# MicrofluidicsController.net
KiCad netlist of a schematic drawn in EAGLE
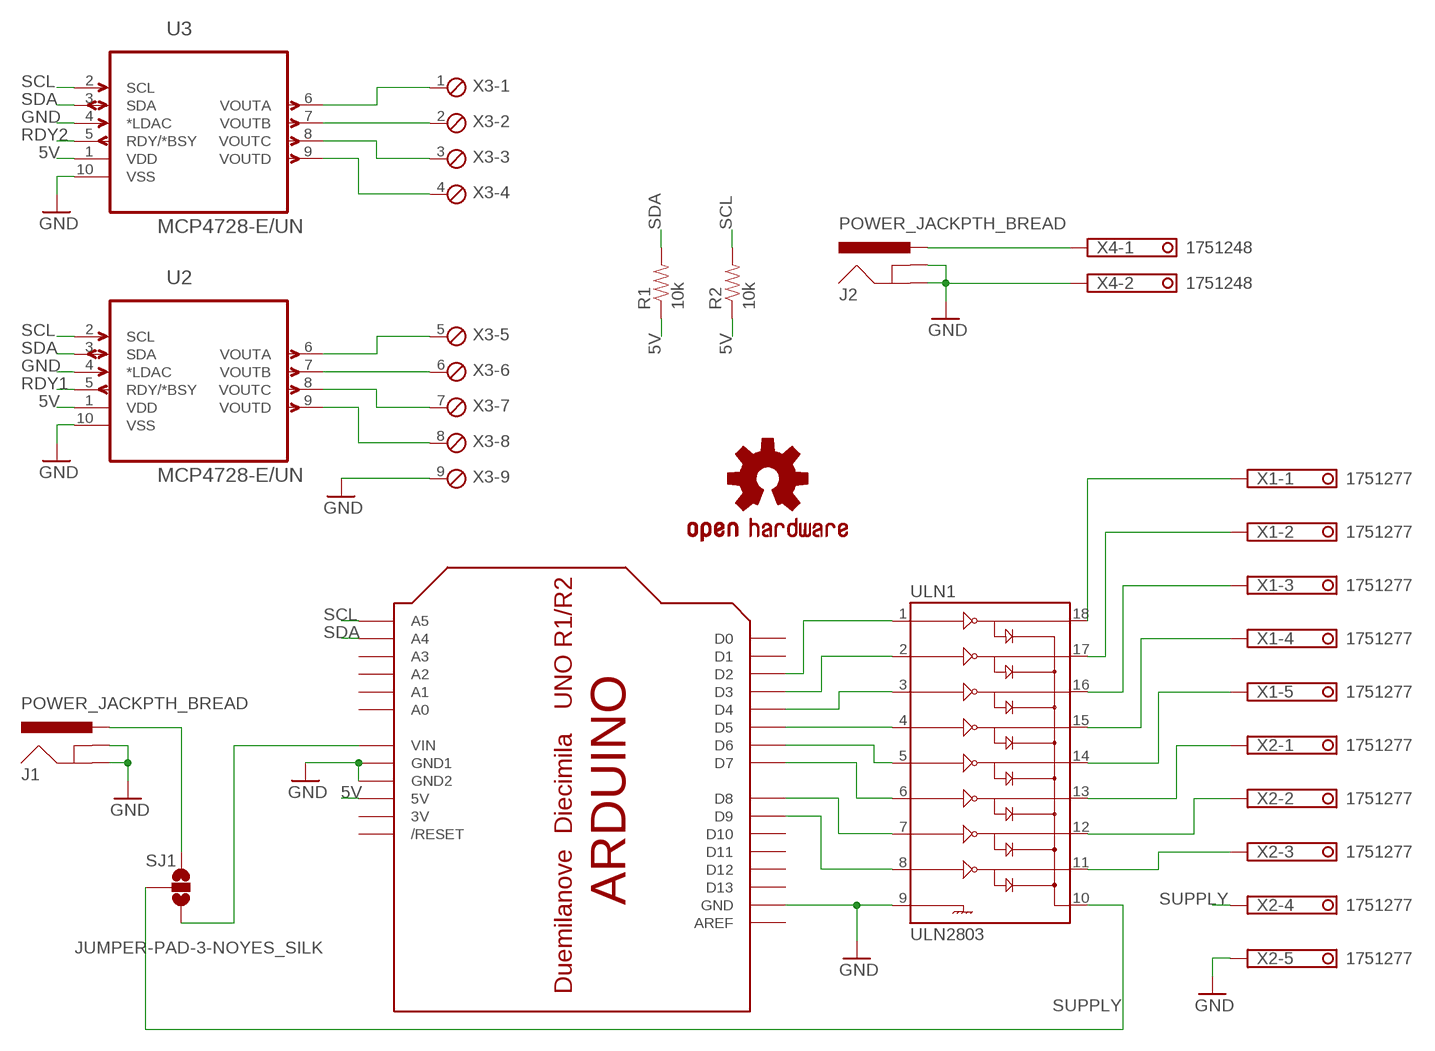
[diagram p0: schematic, sheet 1]

(export (version "E")
  (design (tool "Eeschema 10.0.6"))
  (components
    (comp (ref "J1")
      (value "POWER_JACKPTH_BREAD")
      (footprint "eagle-import:POWER_JACK_PTH_BREAD")
      (libsource (lib "eagle-import") (part "POWER_JACKPTH_BREAD"))
    )
    (comp (ref "J2")
      (value "POWER_JACKPTH_BREAD")
      (footprint "eagle-import:POWER_JACK_PTH_BREAD")
      (libsource (lib "eagle-import") (part "POWER_JACKPTH_BREAD"))
    )
    (comp (ref "LOGO1")
      (value "OSHW-LOGOL")
      (footprint "eagle-import:OSHW-LOGO-L")
      (libsource (lib "eagle-import") (part "OSHW-LOGOL"))
    )
    (comp (ref "R1")
      (value "10k")
      (footprint "eagle-import:0603-RES")
      (libsource (lib "eagle-import") (part "RESISTOR0603-RES"))
    )
    (comp (ref "R2")
      (value "10k")
      (footprint "eagle-import:0603-RES")
      (libsource (lib "eagle-import") (part "RESISTOR0603-RES"))
    )
    (comp (ref "SJ1")
      (value "JUMPER-PAD-3-NOYES_SILK")
      (footprint "eagle-import:PAD-JUMPER-3-NO_YES_SILK")
      (libsource (lib "eagle-import") (part "JUMPER-PAD-3-NOYES_SILK"))
    )
    (comp (ref "U$1")
      (value "ARDUINOUNO")
      (footprint "eagle-import:ARDUINO")
      (libsource (lib "eagle-import") (part "ARDUINOUNO"))
    )
    (comp (ref "U2")
      (value "MCP4728-E/UN")
      (footprint "eagle-import:SOP50P490X110-10N")
      (libsource (lib "eagle-import") (part "MCP4728-E/UN"))
    )
    (comp (ref "U3")
      (value "MCP4728-E/UN")
      (footprint "eagle-import:SOP50P490X110-10N")
      (libsource (lib "eagle-import") (part "MCP4728-E/UN"))
    )
    (comp (ref "ULN1")
      (value "ULN2803")
      (footprint "eagle-import:DIL18")
      (libsource (lib "eagle-import") (part "ULN2803DIP"))
    )
    (comp (ref "X1")
      (value "1751277")
      (footprint "eagle-import:1751277")
      (libsource (lib "eagle-import") (part "1751277"))
    )
    (comp (ref "X2")
      (value "1751277")
      (footprint "eagle-import:1751277")
      (libsource (lib "eagle-import") (part "1751277"))
    )
    (comp (ref "X3")
      (value "MPT9")
      (footprint "eagle-import:9POL254")
      (libsource (lib "eagle-import") (part "MPT9"))
    )
    (comp (ref "X4")
      (value "1751248")
      (footprint "eagle-import:1751248")
      (libsource (lib "eagle-import") (part "1751248"))
    )
  )
  (nets
    (net (code "1") (name "/3V") (class "Default")
      (node (ref "U$1") (pin "3V") (pinfunction "3V_3V") (pintype "power_in"))
    )
    (net (code "2") (name "/5V") (class "Default")
      (node (ref "R1") (pin "1") (pinfunction "1_1") (pintype "passive"))
      (node (ref "R2") (pin "1") (pinfunction "1_1") (pintype "passive"))
      (node (ref "U$1") (pin "5V") (pinfunction "5V_5V") (pintype "power_in"))
      (node (ref "U2") (pin "1") (pinfunction "VDD_1") (pintype "power_in"))
      (node (ref "U3") (pin "1") (pinfunction "VDD_1") (pintype "power_in"))
    )
    (net (code "3") (name "/RDY1") (class "Default")
      (node (ref "U2") (pin "5") (pinfunction "RDY/*BSY_5") (pintype "output"))
    )
    (net (code "4") (name "/RDY2") (class "Default")
      (node (ref "U3") (pin "5") (pinfunction "RDY/*BSY_5") (pintype "output"))
    )
    (net (code "5") (name "/SCL") (class "Default")
      (node (ref "R2") (pin "2") (pinfunction "2_2") (pintype "passive"))
      (node (ref "U$1") (pin "A5") (pinfunction "A5_A5") (pintype "bidirectional"))
      (node (ref "U2") (pin "2") (pinfunction "SCL_2") (pintype "input"))
      (node (ref "U3") (pin "2") (pinfunction "SCL_2") (pintype "input"))
    )
    (net (code "6") (name "/SDA") (class "Default")
      (node (ref "R1") (pin "2") (pinfunction "2_2") (pintype "passive"))
      (node (ref "U$1") (pin "A4") (pinfunction "A4_A4") (pintype "bidirectional"))
      (node (ref "U2") (pin "3") (pinfunction "SDA_3") (pintype "bidirectional"))
      (node (ref "U3") (pin "3") (pinfunction "SDA_3") (pintype "bidirectional"))
    )
    (net (code "7") (name "/SUPPLY") (class "Default")
      (node (ref "SJ1") (pin "2") (pinfunction "2_2") (pintype "passive"))
      (node (ref "ULN1") (pin "10") (pinfunction "10_10") (pintype "bidirectional"))
      (node (ref "X2") (pin "4") (pinfunction "K_4") (pintype "passive"))
    )
    (net (code "8") (name "GND") (class "Default")
      (node (ref "J1") (pin "GND") (pinfunction "GND_GND") (pintype "bidirectional"))
      (node (ref "J1") (pin "GNDBREAK") (pinfunction "GNDBREAK_GNDBREAK") (pintype "bidirectional"))
      (node (ref "J2") (pin "GND") (pinfunction "GND_GND") (pintype "bidirectional"))
      (node (ref "J2") (pin "GNDBREAK") (pinfunction "GNDBREAK_GNDBREAK") (pintype "bidirectional"))
      (node (ref "U$1") (pin "GND") (pinfunction "GND_GND") (pintype "power_in"))
      (node (ref "U$1") (pin "GND1") (pinfunction "GND1_GND1") (pintype "power_in"))
      (node (ref "U$1") (pin "GND2") (pinfunction "GND2_GND2") (pintype "power_in"))
      (node (ref "U2") (pin "10") (pinfunction "VSS_10") (pintype "power_in"))
      (node (ref "U2") (pin "4") (pinfunction "*LDAC_4") (pintype "input"))
      (node (ref "U3") (pin "10") (pinfunction "VSS_10") (pintype "power_in"))
      (node (ref "U3") (pin "4") (pinfunction "*LDAC_4") (pintype "input"))
      (node (ref "ULN1") (pin "9") (pinfunction "9_9") (pintype "bidirectional"))
      (node (ref "X2") (pin "5") (pinfunction "K_5") (pintype "passive"))
      (node (ref "X3") (pin "9") (pinfunction "1_9") (pintype "passive"))
      (node (ref "X4") (pin "2") (pinfunction "K_2") (pintype "passive"))
    )
    (net (code "9") (name "Net-(J1-PadPWR)") (class "Default")
      (node (ref "J1") (pin "PWR") (pinfunction "PWR_PWR") (pintype "bidirectional"))
      (node (ref "SJ1") (pin "1") (pinfunction "1_1") (pintype "passive"))
    )
    (net (code "10") (name "Net-(SJ1-Pad3)") (class "Default")
      (node (ref "SJ1") (pin "3") (pinfunction "3_3") (pintype "passive"))
      (node (ref "U$1") (pin "VIN") (pinfunction "VIN_VIN") (pintype "power_in"))
    )
    (net (code "11") (name "Net-(U$1-PadD2)") (class "Default")
      (node (ref "U$1") (pin "D2") (pinfunction "D2_D2") (pintype "bidirectional"))
      (node (ref "ULN1") (pin "1") (pinfunction "1_1") (pintype "bidirectional"))
    )
    (net (code "12") (name "Net-(U$1-PadD3)") (class "Default")
      (node (ref "U$1") (pin "D3") (pinfunction "D3_D3") (pintype "bidirectional"))
      (node (ref "ULN1") (pin "2") (pinfunction "2_2") (pintype "bidirectional"))
    )
    (net (code "13") (name "Net-(U$1-PadD4)") (class "Default")
      (node (ref "U$1") (pin "D4") (pinfunction "D4_D4") (pintype "bidirectional"))
      (node (ref "ULN1") (pin "3") (pinfunction "3_3") (pintype "bidirectional"))
    )
    (net (code "14") (name "Net-(U$1-PadD5)") (class "Default")
      (node (ref "U$1") (pin "D5") (pinfunction "D5_D5") (pintype "bidirectional"))
      (node (ref "ULN1") (pin "4") (pinfunction "4_4") (pintype "bidirectional"))
    )
    (net (code "15") (name "Net-(U$1-PadD6)") (class "Default")
      (node (ref "U$1") (pin "D6") (pinfunction "D6_D6") (pintype "bidirectional"))
      (node (ref "ULN1") (pin "5") (pinfunction "5_5") (pintype "bidirectional"))
    )
    (net (code "16") (name "Net-(U$1-PadD7)") (class "Default")
      (node (ref "U$1") (pin "D7") (pinfunction "D7_D7") (pintype "bidirectional"))
      (node (ref "ULN1") (pin "6") (pinfunction "6_6") (pintype "bidirectional"))
    )
    (net (code "17") (name "Net-(U$1-PadD8)") (class "Default")
      (node (ref "U$1") (pin "D8") (pinfunction "D8_D8") (pintype "bidirectional"))
      (node (ref "ULN1") (pin "7") (pinfunction "7_7") (pintype "bidirectional"))
    )
    (net (code "18") (name "Net-(U$1-PadD9)") (class "Default")
      (node (ref "U$1") (pin "D9") (pinfunction "D9_D9") (pintype "bidirectional"))
      (node (ref "ULN1") (pin "8") (pinfunction "8_8") (pintype "bidirectional"))
    )
    (net (code "19") (name "Net-(U2-VOUTA)") (class "Default")
      (node (ref "U2") (pin "6") (pinfunction "VOUTA_6") (pintype "output"))
      (node (ref "X3") (pin "5") (pinfunction "1_5") (pintype "passive"))
    )
    (net (code "20") (name "Net-(U2-VOUTB)") (class "Default")
      (node (ref "U2") (pin "7") (pinfunction "VOUTB_7") (pintype "output"))
      (node (ref "X3") (pin "6") (pinfunction "1_6") (pintype "passive"))
    )
    (net (code "21") (name "Net-(U2-VOUTC)") (class "Default")
      (node (ref "U2") (pin "8") (pinfunction "VOUTC_8") (pintype "output"))
      (node (ref "X3") (pin "7") (pinfunction "1_7") (pintype "passive"))
    )
    (net (code "22") (name "Net-(U2-VOUTD)") (class "Default")
      (node (ref "U2") (pin "9") (pinfunction "VOUTD_9") (pintype "output"))
      (node (ref "X3") (pin "8") (pinfunction "1_8") (pintype "passive"))
    )
    (net (code "23") (name "Net-(U3-VOUTA)") (class "Default")
      (node (ref "U3") (pin "6") (pinfunction "VOUTA_6") (pintype "output"))
      (node (ref "X3") (pin "1") (pinfunction "1_1") (pintype "passive"))
    )
    (net (code "24") (name "Net-(U3-VOUTB)") (class "Default")
      (node (ref "U3") (pin "7") (pinfunction "VOUTB_7") (pintype "output"))
      (node (ref "X3") (pin "2") (pinfunction "1_2") (pintype "passive"))
    )
    (net (code "25") (name "Net-(U3-VOUTC)") (class "Default")
      (node (ref "U3") (pin "8") (pinfunction "VOUTC_8") (pintype "output"))
      (node (ref "X3") (pin "3") (pinfunction "1_3") (pintype "passive"))
    )
    (net (code "26") (name "Net-(U3-VOUTD)") (class "Default")
      (node (ref "U3") (pin "9") (pinfunction "VOUTD_9") (pintype "output"))
      (node (ref "X3") (pin "4") (pinfunction "1_4") (pintype "passive"))
    )
    (net (code "27") (name "Net-(X1A-K)") (class "Default")
      (node (ref "ULN1") (pin "18") (pinfunction "18_18") (pintype "bidirectional"))
      (node (ref "X1") (pin "1") (pinfunction "K_1") (pintype "passive"))
    )
    (net (code "28") (name "Net-(X1B-K)") (class "Default")
      (node (ref "ULN1") (pin "17") (pinfunction "17_17") (pintype "bidirectional"))
      (node (ref "X1") (pin "2") (pinfunction "K_2") (pintype "passive"))
    )
    (net (code "29") (name "Net-(X1C-K)") (class "Default")
      (node (ref "ULN1") (pin "16") (pinfunction "16_16") (pintype "bidirectional"))
      (node (ref "X1") (pin "3") (pinfunction "K_3") (pintype "passive"))
    )
    (net (code "30") (name "Net-(X1D-K)") (class "Default")
      (node (ref "ULN1") (pin "15") (pinfunction "15_15") (pintype "bidirectional"))
      (node (ref "X1") (pin "4") (pinfunction "K_4") (pintype "passive"))
    )
    (net (code "31") (name "Net-(X1E-K)") (class "Default")
      (node (ref "ULN1") (pin "14") (pinfunction "14_14") (pintype "bidirectional"))
      (node (ref "X1") (pin "5") (pinfunction "K_5") (pintype "passive"))
    )
    (net (code "32") (name "Net-(X2A-K)") (class "Default")
      (node (ref "ULN1") (pin "13") (pinfunction "13_13") (pintype "bidirectional"))
      (node (ref "X2") (pin "1") (pinfunction "K_1") (pintype "passive"))
    )
    (net (code "33") (name "Net-(X2B-K)") (class "Default")
      (node (ref "ULN1") (pin "12") (pinfunction "12_12") (pintype "bidirectional"))
      (node (ref "X2") (pin "2") (pinfunction "K_2") (pintype "passive"))
    )
    (net (code "34") (name "Net-(X2C-K)") (class "Default")
      (node (ref "ULN1") (pin "11") (pinfunction "11_11") (pintype "bidirectional"))
      (node (ref "X2") (pin "3") (pinfunction "K_3") (pintype "passive"))
    )
    (net (code "35") (name "Net-(X4A-K)") (class "Default")
      (node (ref "J2") (pin "PWR") (pinfunction "PWR_PWR") (pintype "bidirectional"))
      (node (ref "X4") (pin "1") (pinfunction "K_1") (pintype "passive"))
    )
    (net (code "36") (name "unconnected-(U$1-PadA0)") (class "Default")
      (node (ref "U$1") (pin "A0") (pinfunction "A0_A0") (pintype "bidirectional"))
    )
    (net (code "37") (name "unconnected-(U$1-PadA1)") (class "Default")
      (node (ref "U$1") (pin "A1") (pinfunction "A1_A1") (pintype "bidirectional"))
    )
    (net (code "38") (name "unconnected-(U$1-PadA2)") (class "Default")
      (node (ref "U$1") (pin "A2") (pinfunction "A2_A2") (pintype "bidirectional"))
    )
    (net (code "39") (name "unconnected-(U$1-PadA3)") (class "Default")
      (node (ref "U$1") (pin "A3") (pinfunction "A3_A3") (pintype "bidirectional"))
    )
    (net (code "40") (name "unconnected-(U$1-PadAREF)") (class "Default")
      (node (ref "U$1") (pin "AREF") (pinfunction "AREF_AREF") (pintype "bidirectional"))
    )
    (net (code "41") (name "unconnected-(U$1-PadD0)") (class "Default")
      (node (ref "U$1") (pin "D0") (pinfunction "D0_D0") (pintype "bidirectional"))
    )
    (net (code "42") (name "unconnected-(U$1-PadD1)") (class "Default")
      (node (ref "U$1") (pin "D1") (pinfunction "D1_D1") (pintype "bidirectional"))
    )
    (net (code "43") (name "unconnected-(U$1-PadD10)") (class "Default")
      (node (ref "U$1") (pin "D10") (pinfunction "D10_D10") (pintype "bidirectional"))
    )
    (net (code "44") (name "unconnected-(U$1-PadD11)") (class "Default")
      (node (ref "U$1") (pin "D11") (pinfunction "D11_D11") (pintype "bidirectional"))
    )
    (net (code "45") (name "unconnected-(U$1-PadD12)") (class "Default")
      (node (ref "U$1") (pin "D12") (pinfunction "D12_D12") (pintype "bidirectional"))
    )
    (net (code "46") (name "unconnected-(U$1-PadD13)") (class "Default")
      (node (ref "U$1") (pin "D13") (pinfunction "D13_D13") (pintype "bidirectional"))
    )
    (net (code "47") (name "unconnected-(U$1-{slash}RESET-PadRESET)") (class "Default")
      (node (ref "U$1") (pin "RESET") (pinfunction "/RESET_RESET") (pintype "bidirectional"))
    )
  )
)
